# PPU2.net
KiCad netlist of a schematic drawn in Altium Designer
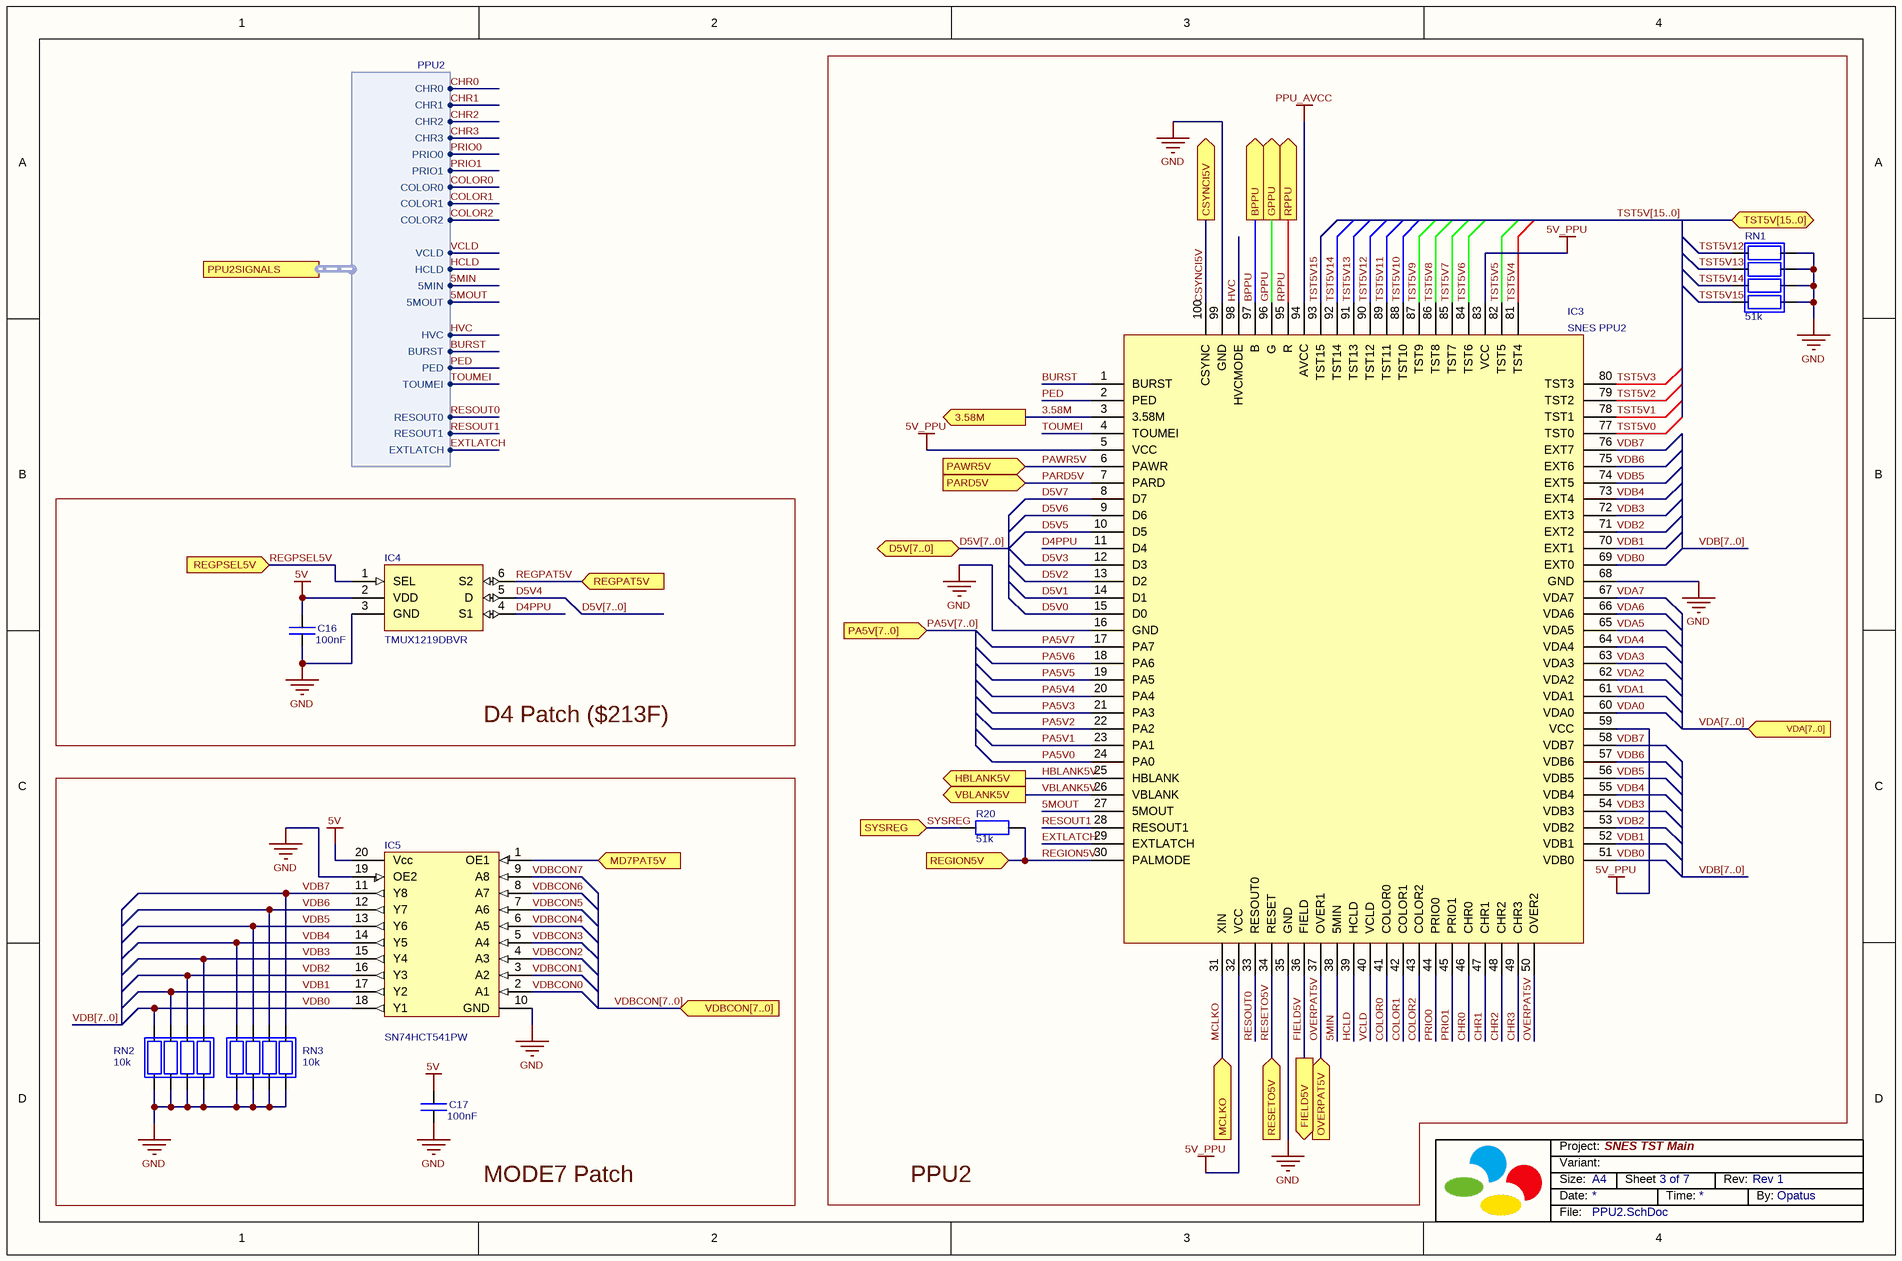
[diagram p0: PPU2.SchDoc]

(export (version "E")
  (design (tool "Eeschema 10.0.6"))
  (components
    (comp (ref "C16")
      (value "100nF")
      (footprint "Cap_0402_Chip")
      (fields
        (field (name "TOLERANCE") "±20%")
        (field (name "Comment") "Ceramic Capacitor 100nF 10V ±20% X7R 0402")
      )
      (libsource (lib "PCB") (part "Capacitor"))
    )
    (comp (ref "C17")
      (value "100nF")
      (footprint "Cap_0402_Chip")
      (fields
        (field (name "TOLERANCE") "±20%")
        (field (name "Comment") "Ceramic Capacitor 100nF 10V ±20% X7R 0402")
      )
      (libsource (lib "PCB") (part "Capacitor"))
    )
    (comp (ref "IC3")
      (value "SNES PPU2")
      (footprint "PPU100Pin")
      (description "PPU2")
      (fields (field (name "MANUFACTURER") "Nintendo"))
      (libsource (lib "PCB") (part "PPU2100Pin"))
    )
    (comp (ref "IC4")
      (value "TMUX1219")
      (footprint "SOT23-6")
      (description "2:1 MUX")
      (fields
        (field (name "MANUFACTURER") "Texas Instruments")
        (field (name "MANUFACTURER_PART_NUMBER") "TMUX1219DBVR")
      )
      (libsource (lib "PCB") (part "TMUX1219"))
    )
    (comp (ref "IC5")
      (value "SN74HCT541")
      (footprint "TSSOP20 Narrow")
      (fields
        (field (name "MANUFACTURER") "Texas Instruments")
        (field (name "MANUFACTURER_PART_NUMBER") "SN74HCT541PW")
      )
      (libsource (lib "PCB") (part "SN74HCT541"))
    )
    (comp (ref "R20")
      (value "51k")
      (footprint "Res_0402_Chip")
      (fields (field (name "TOLERANCE") "±1%") (field (name "Comment") "Resistor 51k 0402 ±1%"))
      (libsource (lib "PCB") (part "R"))
    )
    (comp (ref "RN1")
      (value "51k")
      (footprint "1206_Array_Chip")
      (fields (field (name "TOLERANCE") "±1%") (field (name "Comment") "Resistor Network 51k 1206 ±1%"))
      (libsource (lib "") (part "RNetwork_1"))
    )
    (comp (ref "RN2")
      (value "10k")
      (footprint "1206_Array_Chip")
      (fields (field (name "TOLERANCE") "±1%") (field (name "Comment") "Resistor Network 10k 1206 ±1%"))
      (libsource (lib "PCB") (part "RNetwork"))
    )
    (comp (ref "RN3")
      (value "10k")
      (footprint "1206_Array_Chip")
      (fields (field (name "TOLERANCE") "±1%") (field (name "Comment") "Resistor Network 10k 1206 ±1%"))
      (libsource (lib "PCB") (part "RNetwork"))
    )
  )
  (nets
    (net (code "2") (name "/3.58M") (class "Default")
      (node (ref "IC3") (pin "3") (pinfunction "3.58M_3") (pintype "passive"))
    )
    (net (code "3") (name "/5MIN") (class "Default")
      (node (ref "IC3") (pin "38") (pinfunction "5MIN_38") (pintype "passive"))
    )
    (net (code "4") (name "/5MOUT") (class "Default")
      (node (ref "IC3") (pin "27") (pinfunction "5MOUT_27") (pintype "passive"))
    )
    (net (code "5") (name "/BPPU") (class "Default")
      (node (ref "IC3") (pin "97") (pinfunction "B_97") (pintype "passive"))
    )
    (net (code "6") (name "/BURST") (class "Default")
      (node (ref "IC3") (pin "1") (pinfunction "BURST_1") (pintype "passive"))
    )
    (net (code "7") (name "/CHR0") (class "Default")
      (node (ref "IC3") (pin "46") (pinfunction "CHR0_46") (pintype "passive"))
    )
    (net (code "8") (name "/CHR1") (class "Default")
      (node (ref "IC3") (pin "47") (pinfunction "CHR1_47") (pintype "passive"))
    )
    (net (code "9") (name "/CHR2") (class "Default")
      (node (ref "IC3") (pin "48") (pinfunction "CHR2_48") (pintype "passive"))
    )
    (net (code "10") (name "/CHR3") (class "Default")
      (node (ref "IC3") (pin "49") (pinfunction "CHR3_49") (pintype "passive"))
    )
    (net (code "11") (name "/COLOR0") (class "Default")
      (node (ref "IC3") (pin "41") (pinfunction "COLOR0_41") (pintype "passive"))
    )
    (net (code "12") (name "/COLOR1") (class "Default")
      (node (ref "IC3") (pin "42") (pinfunction "COLOR1_42") (pintype "passive"))
    )
    (net (code "13") (name "/COLOR2") (class "Default")
      (node (ref "IC3") (pin "43") (pinfunction "COLOR2_43") (pintype "passive"))
    )
    (net (code "14") (name "/CSYNCI5V") (class "Default")
      (node (ref "IC3") (pin "100") (pinfunction "CSYNC_100") (pintype "passive"))
    )
    (net (code "15") (name "/D4PPU") (class "Default")
      (node (ref "IC3") (pin "11") (pinfunction "D4_11") (pintype "passive"))
      (node (ref "IC4") (pin "4") (pinfunction "S1_4") (pintype "bidirectional"))
    )
    (net (code "16") (name "/D5V0") (class "Default")
      (node (ref "IC3") (pin "15") (pinfunction "D0_15") (pintype "passive"))
    )
    (net (code "17") (name "/D5V1") (class "Default")
      (node (ref "IC3") (pin "14") (pinfunction "D1_14") (pintype "passive"))
    )
    (net (code "18") (name "/D5V2") (class "Default")
      (node (ref "IC3") (pin "13") (pinfunction "D2_13") (pintype "passive"))
    )
    (net (code "19") (name "/D5V3") (class "Default")
      (node (ref "IC3") (pin "12") (pinfunction "D3_12") (pintype "passive"))
    )
    (net (code "20") (name "/D5V4") (class "Default")
      (node (ref "IC4") (pin "5") (pinfunction "D_5") (pintype "bidirectional"))
    )
    (net (code "21") (name "/D5V5") (class "Default")
      (node (ref "IC3") (pin "10") (pinfunction "D5_10") (pintype "passive"))
    )
    (net (code "22") (name "/D5V6") (class "Default")
      (node (ref "IC3") (pin "9") (pinfunction "D6_9") (pintype "passive"))
    )
    (net (code "23") (name "/D5V7") (class "Default")
      (node (ref "IC3") (pin "8") (pinfunction "D7_8") (pintype "passive"))
    )
    (net (code "25") (name "/EXTLATCH") (class "Default")
      (node (ref "IC3") (pin "29") (pinfunction "EXTLATCH_29") (pintype "passive"))
    )
    (net (code "26") (name "/FIELD5V") (class "Default")
      (node (ref "IC3") (pin "36") (pinfunction "FIELD_36") (pintype "passive"))
    )
    (net (code "27") (name "/GPPU") (class "Default")
      (node (ref "IC3") (pin "96") (pinfunction "G_96") (pintype "passive"))
    )
    (net (code "28") (name "/HBLANK5V") (class "Default")
      (node (ref "IC3") (pin "25") (pinfunction "HBLANK_25") (pintype "passive"))
    )
    (net (code "29") (name "/HCLD") (class "Default")
      (node (ref "IC3") (pin "39") (pinfunction "HCLD_39") (pintype "passive"))
    )
    (net (code "30") (name "/HVC") (class "Default")
      (node (ref "IC3") (pin "98") (pinfunction "HVCMODE_98") (pintype "passive"))
    )
    (net (code "31") (name "/MCLKO") (class "Default")
      (node (ref "IC3") (pin "31") (pinfunction "XIN_31") (pintype "passive"))
    )
    (net (code "32") (name "/MD7PAT5V") (class "Default")
      (node (ref "IC5") (pin "1") (pinfunction "OE1_1") (pintype "input"))
    )
    (net (code "33") (name "/OVERPAT5V") (class "Default")
      (node (ref "IC3") (pin "37") (pinfunction "OVER1_37") (pintype "passive"))
      (node (ref "IC3") (pin "50") (pinfunction "OVER2_50") (pintype "passive"))
    )
    (net (code "34") (name "/PA5V0") (class "Default")
      (node (ref "IC3") (pin "24") (pinfunction "PA0_24") (pintype "passive"))
    )
    (net (code "35") (name "/PA5V1") (class "Default")
      (node (ref "IC3") (pin "23") (pinfunction "PA1_23") (pintype "passive"))
    )
    (net (code "36") (name "/PA5V2") (class "Default")
      (node (ref "IC3") (pin "22") (pinfunction "PA2_22") (pintype "passive"))
    )
    (net (code "37") (name "/PA5V3") (class "Default")
      (node (ref "IC3") (pin "21") (pinfunction "PA3_21") (pintype "passive"))
    )
    (net (code "38") (name "/PA5V4") (class "Default")
      (node (ref "IC3") (pin "20") (pinfunction "PA4_20") (pintype "passive"))
    )
    (net (code "39") (name "/PA5V5") (class "Default")
      (node (ref "IC3") (pin "19") (pinfunction "PA5_19") (pintype "passive"))
    )
    (net (code "40") (name "/PA5V6") (class "Default")
      (node (ref "IC3") (pin "18") (pinfunction "PA6_18") (pintype "passive"))
    )
    (net (code "41") (name "/PA5V7") (class "Default")
      (node (ref "IC3") (pin "17") (pinfunction "PA7_17") (pintype "passive"))
    )
    (net (code "43") (name "/PARD5V") (class "Default")
      (node (ref "IC3") (pin "7") (pinfunction "PARD_7") (pintype "passive"))
    )
    (net (code "44") (name "/PAWR5V") (class "Default")
      (node (ref "IC3") (pin "6") (pinfunction "PAWR_6") (pintype "passive"))
    )
    (net (code "45") (name "/PED") (class "Default")
      (node (ref "IC3") (pin "2") (pinfunction "PED_2") (pintype "passive"))
    )
    (net (code "46") (name "/PRIO0") (class "Default")
      (node (ref "IC3") (pin "44") (pinfunction "PRIO0_44") (pintype "passive"))
    )
    (net (code "47") (name "/PRIO1") (class "Default")
      (node (ref "IC3") (pin "45") (pinfunction "PRIO1_45") (pintype "passive"))
    )
    (net (code "48") (name "/REGION5V") (class "Default")
      (node (ref "IC3") (pin "30") (pinfunction "PALMODE_30") (pintype "passive"))
      (node (ref "R20") (pin "1") (pintype "passive"))
    )
    (net (code "49") (name "/REGPAT5V") (class "Default")
      (node (ref "IC4") (pin "6") (pinfunction "S2_6") (pintype "bidirectional"))
    )
    (net (code "50") (name "/REGPSEL5V") (class "Default")
      (node (ref "IC4") (pin "1") (pinfunction "SEL_1") (pintype "input"))
    )
    (net (code "51") (name "/RESETO5V") (class "Default")
      (node (ref "IC3") (pin "34") (pinfunction "RESET_34") (pintype "passive"))
    )
    (net (code "52") (name "/RESOUT0") (class "Default")
      (node (ref "IC3") (pin "33") (pinfunction "RESOUT0_33") (pintype "passive"))
    )
    (net (code "53") (name "/RESOUT1") (class "Default")
      (node (ref "IC3") (pin "28") (pinfunction "RESOUT1_28") (pintype "passive"))
    )
    (net (code "54") (name "/RPPU") (class "Default")
      (node (ref "IC3") (pin "95") (pinfunction "R_95") (pintype "passive"))
    )
    (net (code "55") (name "/SYSREG") (class "Default") (node (ref "R20") (pin "2") (pintype "passive")))
    (net (code "56") (name "/TOUMEI") (class "Default")
      (node (ref "IC3") (pin "4") (pinfunction "TOUMEI_4") (pintype "passive"))
    )
    (net (code "57") (name "/TST5V0") (class "Default")
      (node (ref "IC3") (pin "77") (pinfunction "TST0_77") (pintype "passive"))
    )
    (net (code "58") (name "/TST5V1") (class "Default")
      (node (ref "IC3") (pin "78") (pinfunction "TST1_78") (pintype "passive"))
    )
    (net (code "59") (name "/TST5V2") (class "Default")
      (node (ref "IC3") (pin "79") (pinfunction "TST2_79") (pintype "passive"))
    )
    (net (code "60") (name "/TST5V3") (class "Default")
      (node (ref "IC3") (pin "80") (pinfunction "TST3_80") (pintype "passive"))
    )
    (net (code "61") (name "/TST5V4") (class "Default")
      (node (ref "IC3") (pin "81") (pinfunction "TST4_81") (pintype "passive"))
    )
    (net (code "62") (name "/TST5V5") (class "Default")
      (node (ref "IC3") (pin "82") (pinfunction "TST5_82") (pintype "passive"))
    )
    (net (code "63") (name "/TST5V6") (class "Default")
      (node (ref "IC3") (pin "84") (pinfunction "TST6_84") (pintype "passive"))
    )
    (net (code "64") (name "/TST5V7") (class "Default")
      (node (ref "IC3") (pin "85") (pinfunction "TST7_85") (pintype "passive"))
    )
    (net (code "65") (name "/TST5V8") (class "Default")
      (node (ref "IC3") (pin "86") (pinfunction "TST8_86") (pintype "passive"))
    )
    (net (code "66") (name "/TST5V9") (class "Default")
      (node (ref "IC3") (pin "87") (pinfunction "TST9_87") (pintype "passive"))
    )
    (net (code "67") (name "/TST5V10") (class "Default")
      (node (ref "IC3") (pin "88") (pinfunction "TST10_88") (pintype "passive"))
    )
    (net (code "68") (name "/TST5V11") (class "Default")
      (node (ref "IC3") (pin "89") (pinfunction "TST11_89") (pintype "passive"))
    )
    (net (code "69") (name "/TST5V12") (class "Default")
      (node (ref "IC3") (pin "90") (pinfunction "TST12_90") (pintype "passive"))
      (node (ref "RN1") (pin "5") (pintype "passive"))
    )
    (net (code "70") (name "/TST5V13") (class "Default")
      (node (ref "IC3") (pin "91") (pinfunction "TST13_91") (pintype "passive"))
      (node (ref "RN1") (pin "6") (pintype "passive"))
    )
    (net (code "71") (name "/TST5V14") (class "Default")
      (node (ref "IC3") (pin "92") (pinfunction "TST14_92") (pintype "passive"))
      (node (ref "RN1") (pin "7") (pintype "passive"))
    )
    (net (code "72") (name "/TST5V15") (class "Default")
      (node (ref "IC3") (pin "93") (pinfunction "TST15_93") (pintype "passive"))
      (node (ref "RN1") (pin "8") (pintype "passive"))
    )
    (net (code "74") (name "/VBLANK5V") (class "Default")
      (node (ref "IC3") (pin "26") (pinfunction "VBLANK_26") (pintype "passive"))
    )
    (net (code "75") (name "/VCLD") (class "Default")
      (node (ref "IC3") (pin "40") (pinfunction "VCLD_40") (pintype "passive"))
    )
    (net (code "76") (name "/VDA0") (class "Default")
      (node (ref "IC3") (pin "60") (pinfunction "VDA0_60") (pintype "passive"))
    )
    (net (code "77") (name "/VDA1") (class "Default")
      (node (ref "IC3") (pin "61") (pinfunction "VDA1_61") (pintype "passive"))
    )
    (net (code "78") (name "/VDA2") (class "Default")
      (node (ref "IC3") (pin "62") (pinfunction "VDA2_62") (pintype "passive"))
    )
    (net (code "79") (name "/VDA3") (class "Default")
      (node (ref "IC3") (pin "63") (pinfunction "VDA3_63") (pintype "passive"))
    )
    (net (code "80") (name "/VDA4") (class "Default")
      (node (ref "IC3") (pin "64") (pinfunction "VDA4_64") (pintype "passive"))
    )
    (net (code "81") (name "/VDA5") (class "Default")
      (node (ref "IC3") (pin "65") (pinfunction "VDA5_65") (pintype "passive"))
    )
    (net (code "82") (name "/VDA6") (class "Default")
      (node (ref "IC3") (pin "66") (pinfunction "VDA6_66") (pintype "passive"))
    )
    (net (code "83") (name "/VDA7") (class "Default")
      (node (ref "IC3") (pin "67") (pinfunction "VDA7_67") (pintype "passive"))
    )
    (net (code "85") (name "/VDB0") (class "Default")
      (node (ref "IC3") (pin "51") (pinfunction "VDB0_51") (pintype "passive"))
      (node (ref "IC3") (pin "69") (pinfunction "EXT0_69") (pintype "passive"))
      (node (ref "IC5") (pin "18") (pinfunction "Y1_18") (pintype "output"))
      (node (ref "RN2") (pin "8") (pintype "passive"))
    )
    (net (code "86") (name "/VDB1") (class "Default")
      (node (ref "IC3") (pin "52") (pinfunction "VDB1_52") (pintype "passive"))
      (node (ref "IC3") (pin "70") (pinfunction "EXT1_70") (pintype "passive"))
      (node (ref "IC5") (pin "17") (pinfunction "Y2_17") (pintype "output"))
      (node (ref "RN2") (pin "7") (pintype "passive"))
    )
    (net (code "87") (name "/VDB2") (class "Default")
      (node (ref "IC3") (pin "53") (pinfunction "VDB2_53") (pintype "passive"))
      (node (ref "IC3") (pin "71") (pinfunction "EXT2_71") (pintype "passive"))
      (node (ref "IC5") (pin "16") (pinfunction "Y3_16") (pintype "output"))
      (node (ref "RN2") (pin "6") (pintype "passive"))
    )
    (net (code "88") (name "/VDB3") (class "Default")
      (node (ref "IC3") (pin "54") (pinfunction "VDB3_54") (pintype "passive"))
      (node (ref "IC3") (pin "72") (pinfunction "EXT3_72") (pintype "passive"))
      (node (ref "IC5") (pin "15") (pinfunction "Y4_15") (pintype "output"))
      (node (ref "RN2") (pin "5") (pintype "passive"))
    )
    (net (code "89") (name "/VDB4") (class "Default")
      (node (ref "IC3") (pin "55") (pinfunction "VDB4_55") (pintype "passive"))
      (node (ref "IC3") (pin "73") (pinfunction "EXT4_73") (pintype "passive"))
      (node (ref "IC5") (pin "14") (pinfunction "Y5_14") (pintype "output"))
      (node (ref "RN3") (pin "8") (pintype "passive"))
    )
    (net (code "90") (name "/VDB5") (class "Default")
      (node (ref "IC3") (pin "56") (pinfunction "VDB5_56") (pintype "passive"))
      (node (ref "IC3") (pin "74") (pinfunction "EXT5_74") (pintype "passive"))
      (node (ref "IC5") (pin "13") (pinfunction "Y6_13") (pintype "output"))
      (node (ref "RN3") (pin "7") (pintype "passive"))
    )
    (net (code "91") (name "/VDB6") (class "Default")
      (node (ref "IC3") (pin "57") (pinfunction "VDB6_57") (pintype "passive"))
      (node (ref "IC3") (pin "75") (pinfunction "EXT6_75") (pintype "passive"))
      (node (ref "IC5") (pin "12") (pinfunction "Y7_12") (pintype "output"))
      (node (ref "RN3") (pin "6") (pintype "passive"))
    )
    (net (code "92") (name "/VDB7") (class "Default")
      (node (ref "IC3") (pin "58") (pinfunction "VDB7_58") (pintype "passive"))
      (node (ref "IC3") (pin "76") (pinfunction "EXT7_76") (pintype "passive"))
      (node (ref "IC5") (pin "11") (pinfunction "Y8_11") (pintype "output"))
      (node (ref "RN3") (pin "5") (pintype "passive"))
    )
    (net (code "93") (name "/VDBCON0") (class "Default")
      (node (ref "IC5") (pin "2") (pinfunction "A1_2") (pintype "input"))
    )
    (net (code "94") (name "/VDBCON1") (class "Default")
      (node (ref "IC5") (pin "3") (pinfunction "A2_3") (pintype "input"))
    )
    (net (code "95") (name "/VDBCON2") (class "Default")
      (node (ref "IC5") (pin "4") (pinfunction "A3_4") (pintype "input"))
    )
    (net (code "96") (name "/VDBCON3") (class "Default")
      (node (ref "IC5") (pin "5") (pinfunction "A4_5") (pintype "input"))
    )
    (net (code "97") (name "/VDBCON4") (class "Default")
      (node (ref "IC5") (pin "6") (pinfunction "A5_6") (pintype "input"))
    )
    (net (code "98") (name "/VDBCON5") (class "Default")
      (node (ref "IC5") (pin "7") (pinfunction "A6_7") (pintype "input"))
    )
    (net (code "99") (name "/VDBCON6") (class "Default")
      (node (ref "IC5") (pin "8") (pinfunction "A7_8") (pintype "input"))
    )
    (net (code "100") (name "/VDBCON7") (class "Default")
      (node (ref "IC5") (pin "9") (pinfunction "A8_9") (pintype "input"))
    )
    (net (code "104") (name "5V") (class "Default")
      (node (ref "C16") (pin "1") (pintype "passive"))
      (node (ref "C17") (pin "1") (pintype "passive"))
      (node (ref "IC4") (pin "2") (pinfunction "VDD_2") (pintype "power_in"))
      (node (ref "IC5") (pin "20") (pinfunction "Vcc_20") (pintype "power_in"))
    )
    (net (code "105") (name "5V_PPU") (class "Default")
      (node (ref "IC3") (pin "32") (pinfunction "VCC_32") (pintype "passive"))
      (node (ref "IC3") (pin "5") (pinfunction "VCC_5") (pintype "passive"))
      (node (ref "IC3") (pin "59") (pinfunction "VCC_59") (pintype "passive"))
      (node (ref "IC3") (pin "83") (pinfunction "VCC_83") (pintype "passive"))
    )
    (net (code "106") (name "GND") (class "Default")
      (node (ref "C16") (pin "2") (pintype "passive"))
      (node (ref "C17") (pin "2") (pintype "passive"))
      (node (ref "IC3") (pin "16") (pinfunction "GND_16") (pintype "passive"))
      (node (ref "IC3") (pin "35") (pinfunction "GND_35") (pintype "passive"))
      (node (ref "IC3") (pin "68") (pinfunction "GND_68") (pintype "passive"))
      (node (ref "IC3") (pin "99") (pinfunction "GND_99") (pintype "passive"))
      (node (ref "IC4") (pin "3") (pinfunction "GND_3") (pintype "power_in"))
      (node (ref "IC5") (pin "10") (pinfunction "GND_10") (pintype "power_in"))
      (node (ref "IC5") (pin "19") (pinfunction "OE2_19") (pintype "input"))
      (node (ref "RN1") (pin "1") (pintype "passive"))
      (node (ref "RN1") (pin "2") (pintype "passive"))
      (node (ref "RN1") (pin "3") (pintype "passive"))
      (node (ref "RN1") (pin "4") (pintype "passive"))
      (node (ref "RN2") (pin "1") (pintype "passive"))
      (node (ref "RN2") (pin "2") (pintype "passive"))
      (node (ref "RN2") (pin "3") (pintype "passive"))
      (node (ref "RN2") (pin "4") (pintype "passive"))
      (node (ref "RN3") (pin "1") (pintype "passive"))
      (node (ref "RN3") (pin "2") (pintype "passive"))
      (node (ref "RN3") (pin "3") (pintype "passive"))
      (node (ref "RN3") (pin "4") (pintype "passive"))
    )
    (net (code "107") (name "PPU_AVCC") (class "Default")
      (node (ref "IC3") (pin "94") (pinfunction "AVCC_94") (pintype "passive"))
    )
  )
)
